# Sheet1.net
KiCad netlist of a schematic drawn in Altium Designer
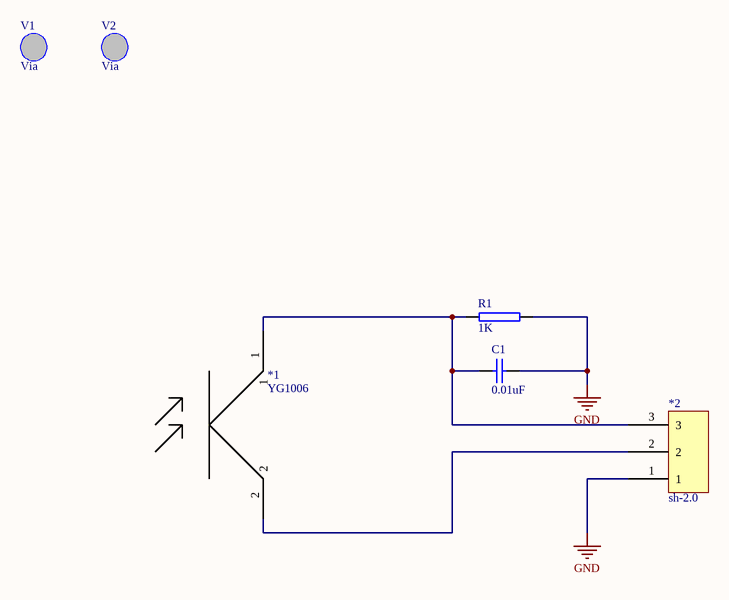
[diagram p0: Sheet1.SchDoc]

(export (version "E")
  (design (tool "Eeschema 10.0.6"))
  (components
    (comp (ref "*1")
      (value "YG1006")
      (footprint "zhangchong:Q")
      (libsource (lib "zhangchong") (part "YG1006"))
    )
    (comp (ref "*2") (value "sh-2.0") (footprint "sh-2.0") (libsource (lib "zhangchong") (part "sh-2.0")))
    (comp (ref "C1")
      (value "0.01uF")
      (footprint "Miscellaneous Devices:1608[0603]")
      (libsource (lib "gupeng_sch") (part "CAP"))
    )
    (comp (ref "R1")
      (value "1K")
      (footprint "Miscellaneous Devices:1608[0603]")
      (libsource (lib "gupeng_sch") (part "RES"))
    )
    (comp (ref "V1") (value "Via") (footprint "zhangchong:Via") (libsource (lib "zhangchong") (part "Via")))
    (comp (ref "V2") (value "Via") (footprint "zhangchong:Via") (libsource (lib "zhangchong") (part "Via")))
  )
  (nets
    (net (code "1") (name "GND") (class "Default")
      (node (ref "*2") (pin "1") (pinfunction "1_1") (pintype "passive"))
      (node (ref "C1") (pin "2") (pinfunction "2_2") (pintype "passive"))
      (node (ref "R1") (pin "2") (pinfunction "2_2") (pintype "passive"))
    )
    (net (code "2") (name "Net-(*1-Pad1)") (class "Default")
      (node (ref "*1") (pin "1") (pinfunction "1_1") (pintype "passive"))
      (node (ref "*2") (pin "3") (pinfunction "3_3") (pintype "passive"))
      (node (ref "C1") (pin "1") (pinfunction "1_1") (pintype "passive"))
      (node (ref "R1") (pin "1") (pinfunction "1_1") (pintype "passive"))
    )
    (net (code "3") (name "Net-(*1-Pad2)") (class "Default")
      (node (ref "*1") (pin "2") (pinfunction "2_2") (pintype "passive"))
      (node (ref "*2") (pin "2") (pinfunction "2_2") (pintype "passive"))
    )
  )
)
